# Sheet_1.net
KiCad netlist of a schematic drawn in Altium Designer
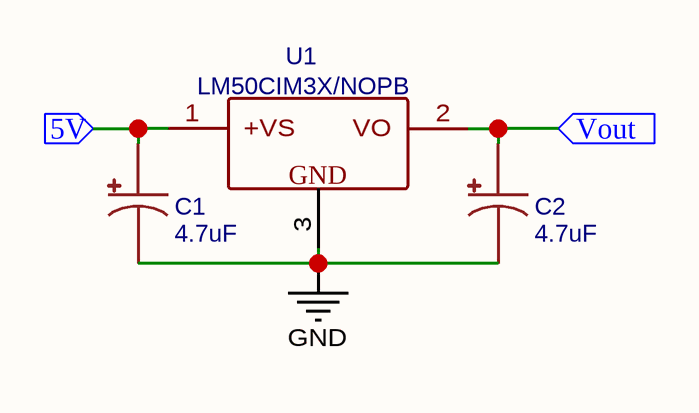
[diagram p0: Sheet_1.schdoc]

(export (version "E")
  (design (tool "Eeschema 10.0.6"))
  (components
    (comp (ref "C1")
      (value "4.7uF")
      (fields
        (field (name "MANUFACTURER") "KEMET(基美)")
        (field (name "MANUFACTURER PART") "T491A475M025AT")
        (field (name "CONTRIBUTOR") "LCSC")
      )
      (libsource (lib "altium-import") (part "root_1_4.7uF_"))
    )
    (comp (ref "C2")
      (value "4.7uF")
      (fields
        (field (name "MANUFACTURER") "KEMET(基美)")
        (field (name "MANUFACTURER PART") "T491A475M025AT")
        (field (name "CONTRIBUTOR") "LCSC")
      )
      (libsource (lib "altium-import") (part "root_1_4.7uF_"))
    )
    (comp (ref "U1")
      (value "LM50CIM3X/NOPB")
      (fields (field (name "MANUFACTURER") "TI(德州仪器)"))
      (libsource (lib "altium-import") (part "root_0_LM50CIM3X/NOPB_"))
    )
  )
  (nets
    (net (code "1") (name "/5V") (class "Default")
      (node (ref "C1") (pin "1") (pinfunction "1_1") (pintype "passive"))
      (node (ref "U1") (pin "1") (pinfunction "+VS_1") (pintype "passive"))
    )
    (net (code "2") (name "/Vout") (class "Default")
      (node (ref "C2") (pin "1") (pinfunction "1_1") (pintype "passive"))
      (node (ref "U1") (pin "2") (pinfunction "VO_2") (pintype "passive"))
    )
    (net (code "3") (name "GND") (class "Default")
      (node (ref "C1") (pin "2") (pinfunction "2_2") (pintype "passive"))
      (node (ref "C2") (pin "2") (pinfunction "2_2") (pintype "passive"))
      (node (ref "U1") (pin "3") (pinfunction "GND_3") (pintype "passive"))
    )
  )
)
